# untitled2.net
KiCad netlist of a schematic drawn in EAGLE
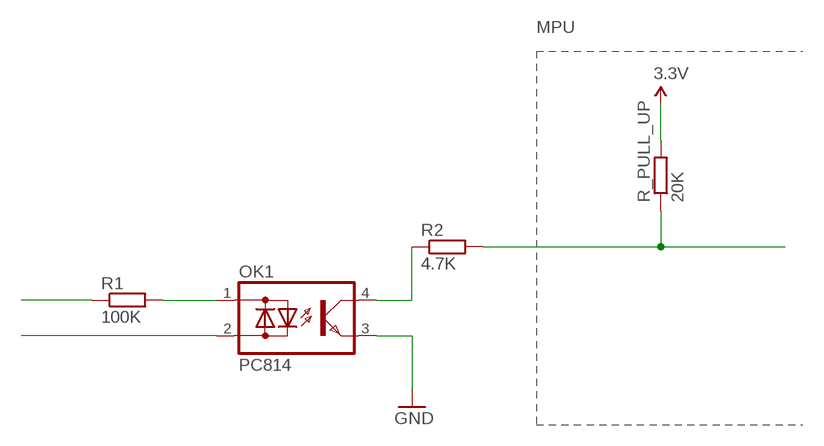
[diagram p0: schematic, sheet 1]

(export (version "E")
  (design (tool "Eeschema 10.0.6"))
  (components
    (comp (ref "OK1")
      (value "PC814")
      (footprint "eagle-import:DIL04")
      (libsource (lib "eagle-import") (part "PC814"))
    )
    (comp (ref "R1")
      (value "100K")
      (footprint "eagle-import:0204V")
      (libsource (lib "eagle-import") (part "R-EU_0204/2V"))
    )
    (comp (ref "R2")
      (value "4.7K")
      (footprint "eagle-import:0204V")
      (libsource (lib "eagle-import") (part "R-EU_0204/2V"))
    )
    (comp (ref "R_PULL_UP")
      (value "20K")
      (footprint "eagle-import:0204V")
      (libsource (lib "eagle-import") (part "R-EU_0204/2V"))
    )
  )
  (nets
    (net (code "1") (name "3.3V") (class "Default")
      (node (ref "R_PULL_UP") (pin "2") (pinfunction "2_2") (pintype "passive"))
    )
    (net (code "2") (name "GND") (class "Default")
      (node (ref "OK1") (pin "3") (pinfunction "E_3") (pintype "passive"))
    )
    (net (code "3") (name "Net-(OK1-AC1)") (class "Default")
      (node (ref "OK1") (pin "1") (pinfunction "AC1_1") (pintype "passive"))
      (node (ref "R1") (pin "2") (pinfunction "2_2") (pintype "passive"))
    )
    (net (code "4") (name "Net-(OK1-C)") (class "Default")
      (node (ref "OK1") (pin "4") (pinfunction "C_4") (pintype "passive"))
      (node (ref "R2") (pin "1") (pinfunction "1_1") (pintype "passive"))
    )
    (net (code "5") (name "Net-(R2-Pad2)") (class "Default")
      (node (ref "R2") (pin "2") (pinfunction "2_2") (pintype "passive"))
      (node (ref "R_PULL_UP") (pin "1") (pinfunction "1_1") (pintype "passive"))
    )
    (net (code "6") (name "unconnected-(OK1-AC2-Pad2)") (class "Default")
      (node (ref "OK1") (pin "2") (pinfunction "AC2_2") (pintype "passive"))
    )
    (net (code "7") (name "unconnected-(R1-Pad1)") (class "Default")
      (node (ref "R1") (pin "1") (pinfunction "1_1") (pintype "passive"))
    )
  )
)
